# ProPrj__3_1_MIPI.net
KiCad netlist of a schematic drawn in EasyEDA Pro
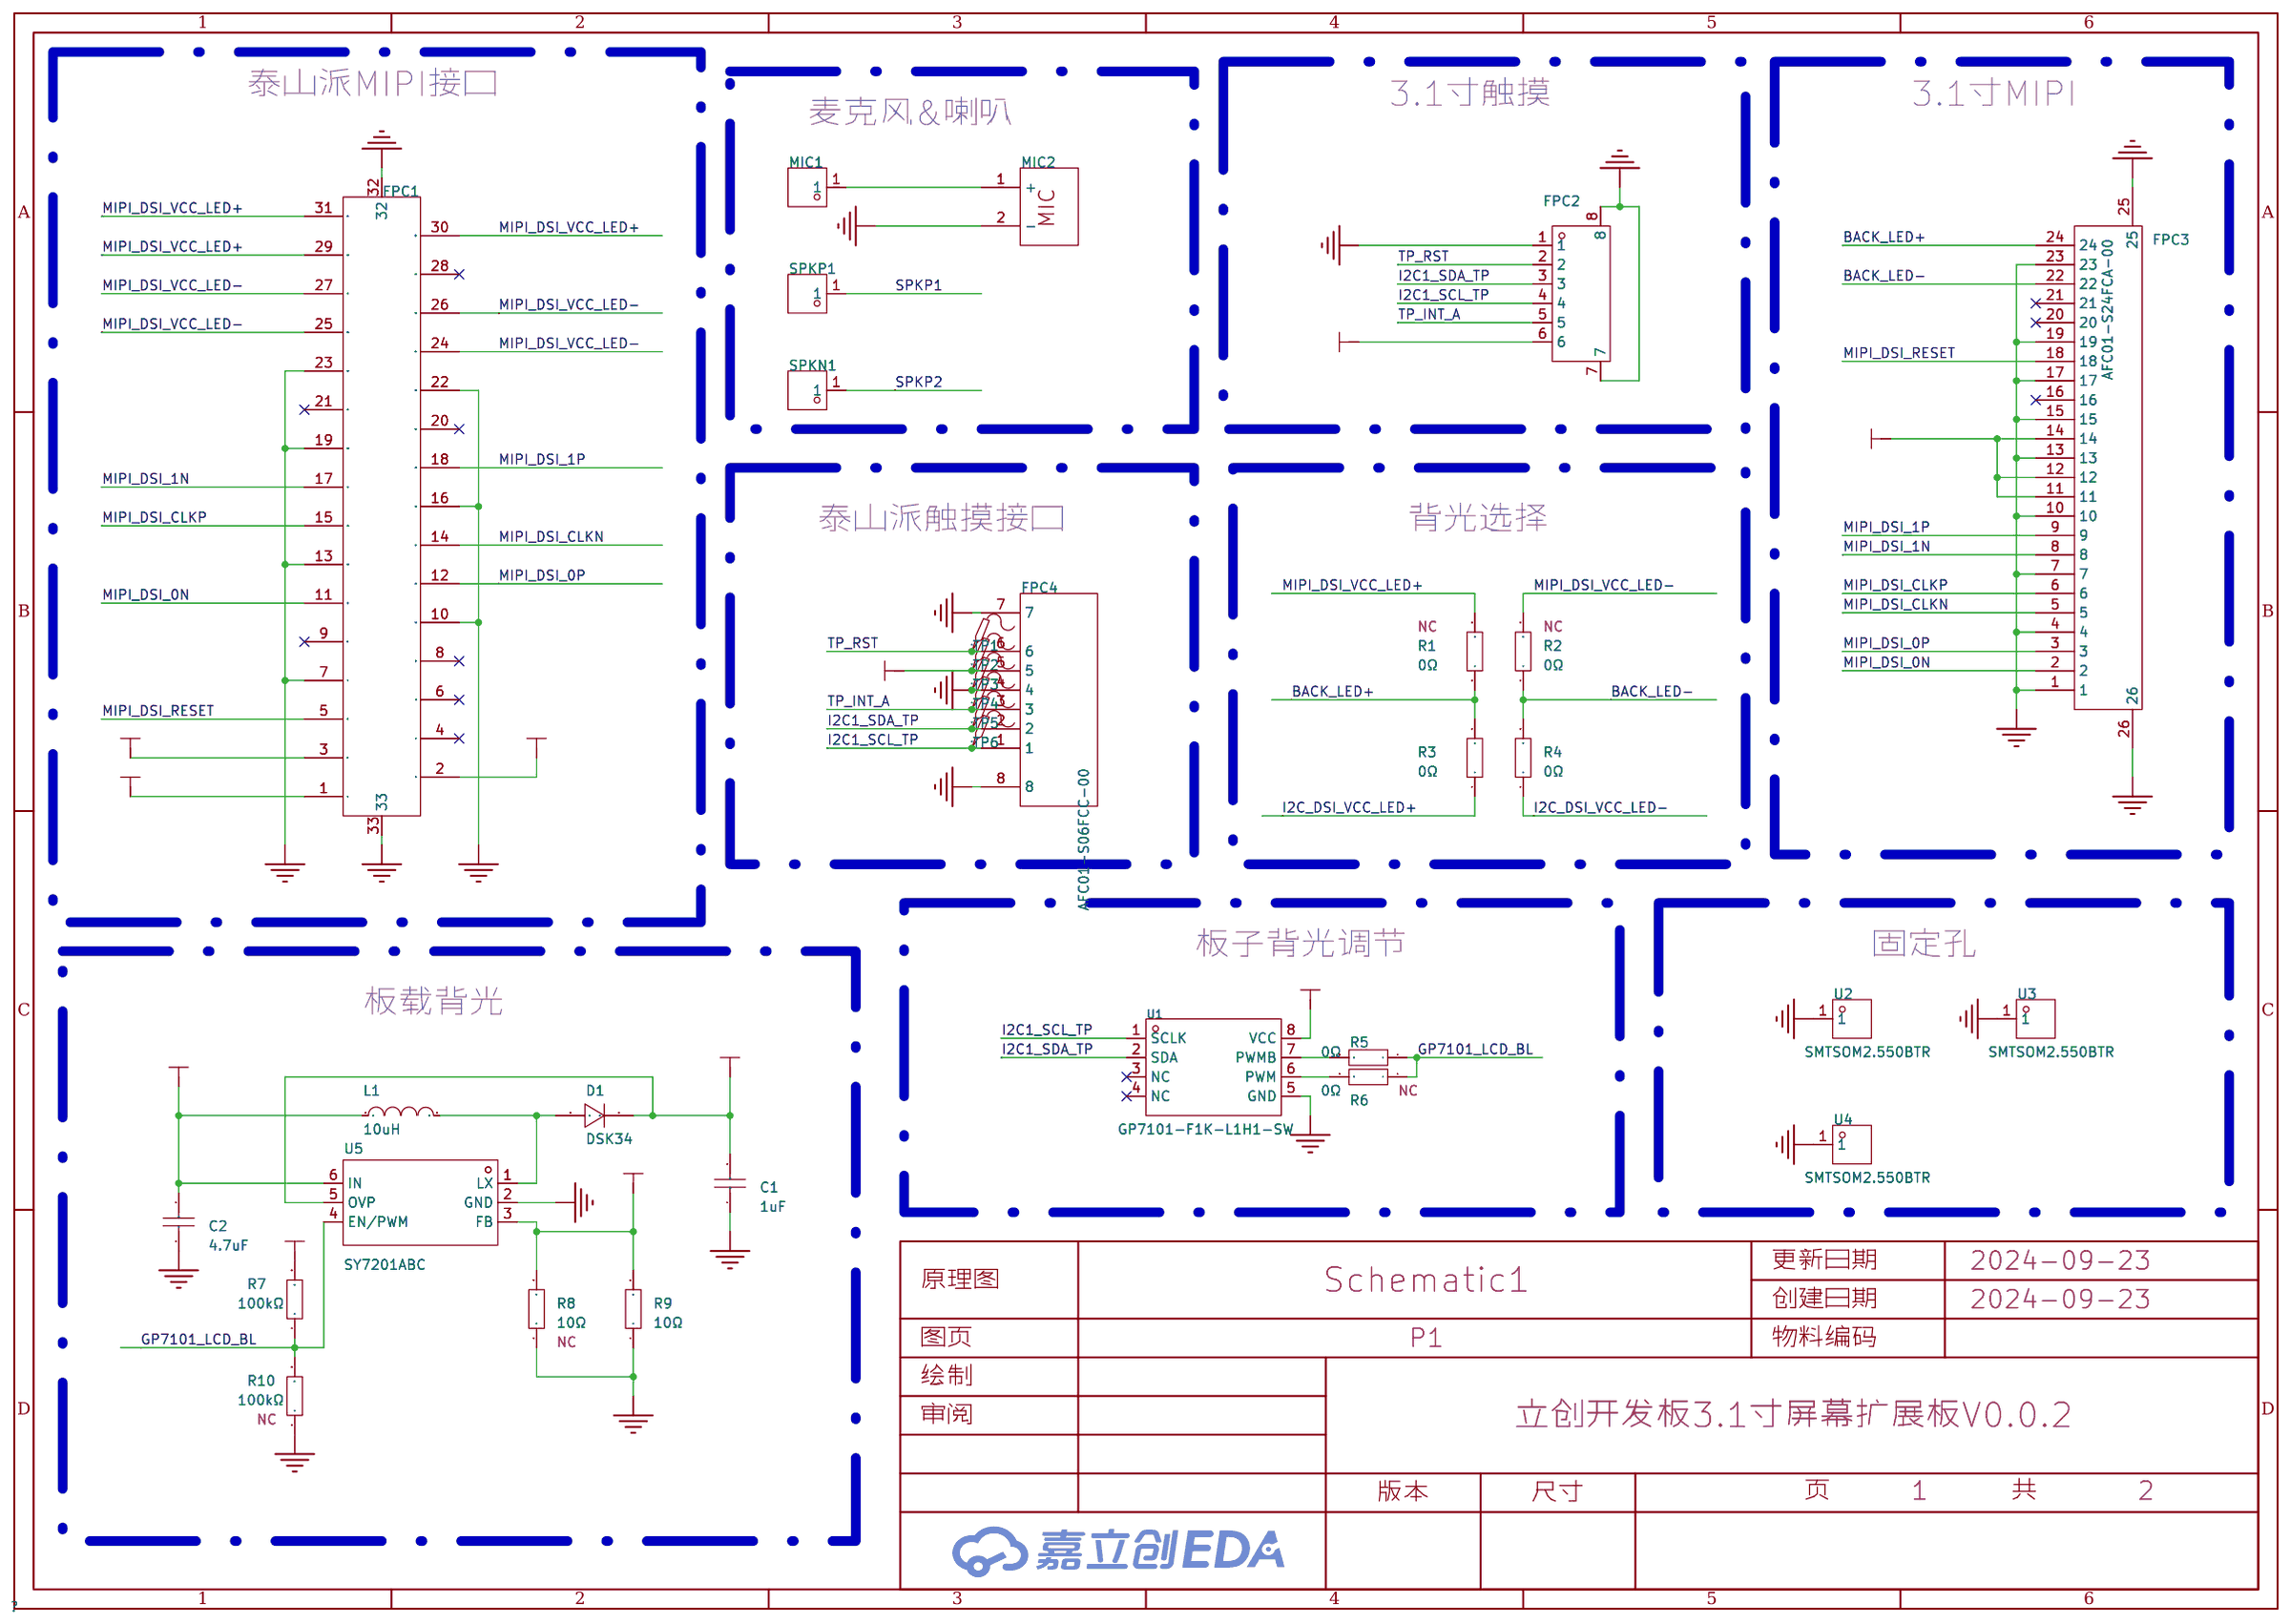
[diagram p0: P1]
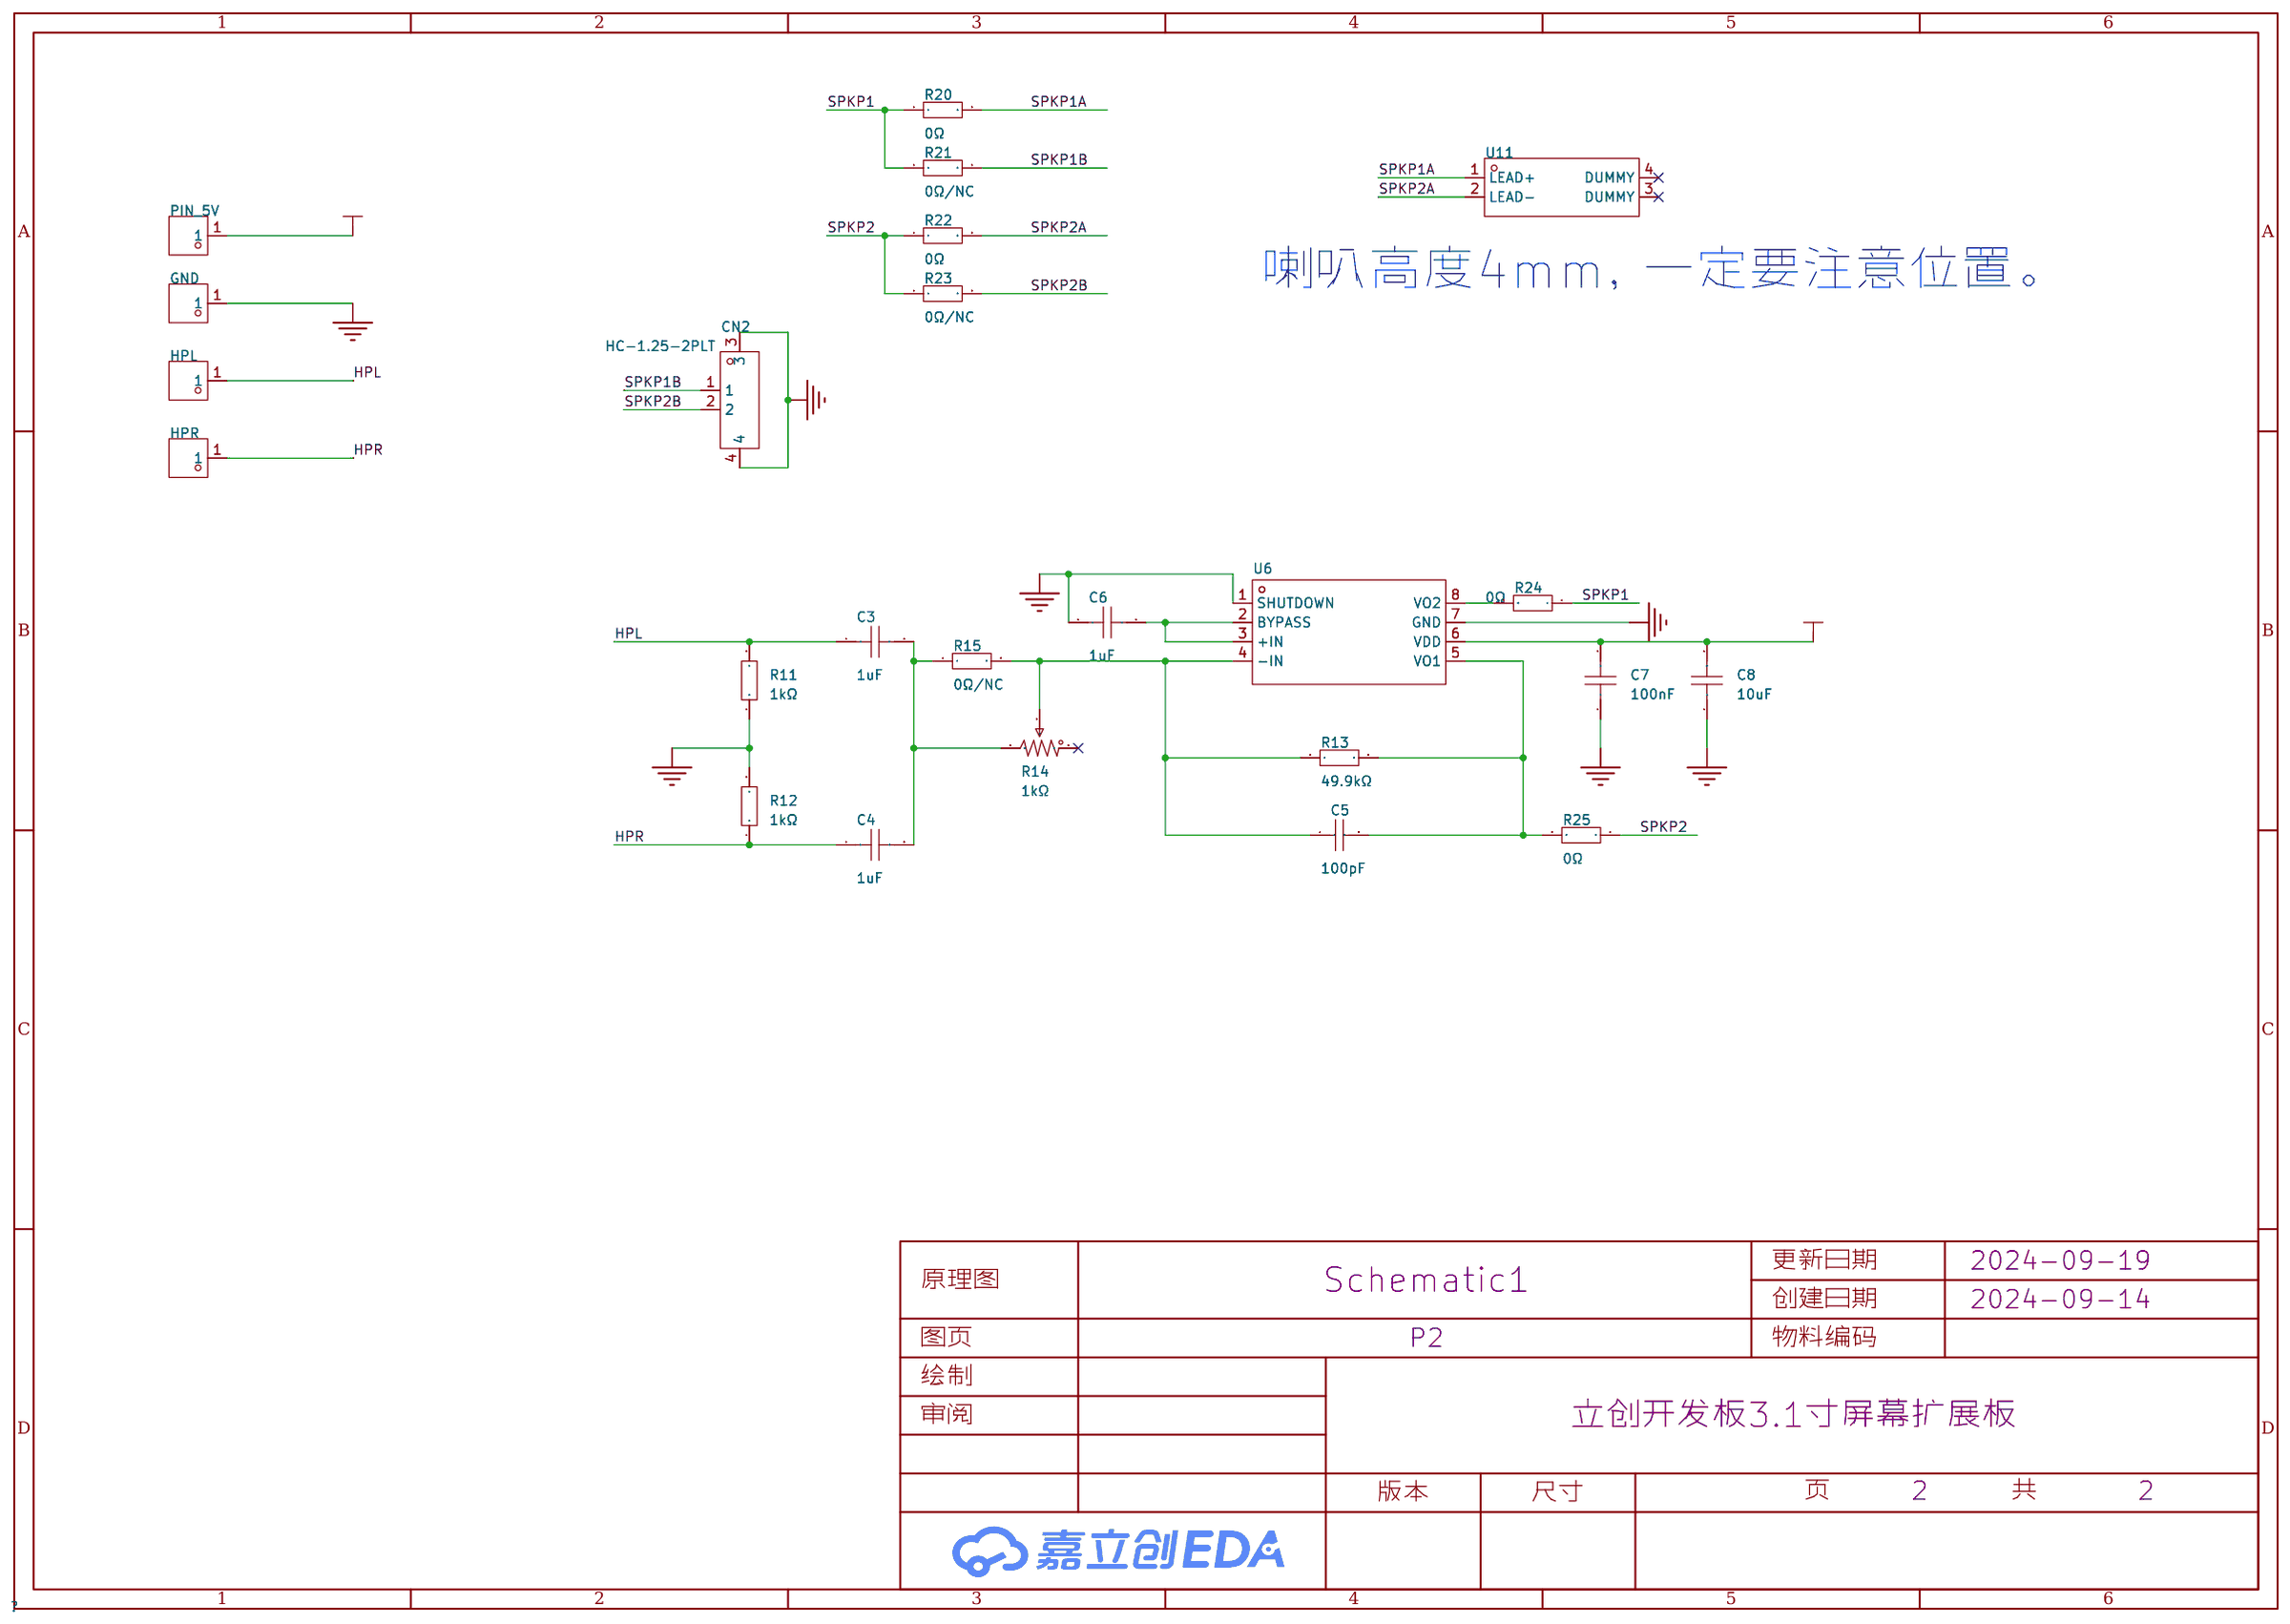
[diagram p1: P2]

(export (version "E")
  (design (tool "Eeschema 10.0.6"))
  (components
    (comp (ref "C1")
      (value "1uF")
      (footprint "easyedapro:C0805")
      (description "容值:1uF;精度:±10%;额定电压:50V;材质(温度系数):X7R;")
      (fields
        (field (name "Manufacturer Part") "CL21B105KBFNNNE")
        (field (name "Manufacturer") "SAMSUNG(三星)")
      )
      (libsource (lib "easyedapro") (part "CL21B105KBFNNNE"))
    )
    (comp (ref "C2")
      (value "4.7uF")
      (footprint "easyedapro:C0805")
      (description "容值:4.7uF;精度:±10%;额定电压:25V;材质(温度系数):X5R;")
      (fields
        (field (name "Manufacturer Part") "CL21A475KAQNNNE")
        (field (name "Manufacturer") "SAMSUNG(三星)")
      )
      (libsource (lib "easyedapro") (part "CL21A475KAQNNNE"))
    )
    (comp (ref "D1")
      (value "DSK34")
      (description "二极管配置:-;直流反向耐压(Vr):1kV;平均整流电流(Io):1A;正向压降(Vf):1.1V@1A;反向电流(Ir):10uA@1kV;")
      (fields (field (name "Manufacturer") "TWGMC(台湾迪嘉)"))
      (libsource (lib "easyedapro") (part "sm4007pl"))
    )
    (comp (ref "FPC1")
      (value "AFE03-S31FMA-1H")
      (footprint "easyedapro:FPC-SMD_P0.30-31P_FGS-XJ-H1.0")
      (description "间距:0.3mm;触点数量:31;锁定特性:翻盖式;安装类型:卧贴;触点类型:下接;")
      (fields (field (name "Manufacturer") "JS(钜硕电子)"))
      (libsource (lib "easyedapro") (part "AFE03-S31FMA-1H"))
    )
    (comp (ref "FPC2")
      (value "FPC-05F-6PH20")
      (footprint "easyedapro:FPC-SMD_6P-P0.50_XUNPU_FPC-05F-6PH20")
      (description "间距:0.5mm;触点数量:6P;锁定特性:翻盖式;触点类型:下接;安装类型:卧贴;工作温度范围:-25°C~+85°C;")
      (fields (field (name "Manufacturer") "XUNPU(讯普)"))
      (libsource (lib "easyedapro") (part "FPC-05F-6PH20"))
    )
    (comp (ref "FPC3")
      (value "AFC01-S24FCA-00")
      (footprint "easyedapro:FPC-SMD_P0.50-24P_FGS-XJ-H2.0")
      (description "间距:0.5mm;触点数量:24P;锁定特性:翻盖式;触点类型:下接;安装类型:卧贴;")
      (fields (field (name "Manufacturer") "JS(钜硕电子)"))
      (libsource (lib "easyedapro") (part "AFC01-S24FCA-00"))
    )
    (comp (ref "FPC4")
      (value "AFC01-S06FCC-00")
      (footprint "easyedapro:FPC-SMD_AFC01-S06FCC-00")
      (description "间距:0.5mm;触点数量:6;锁定特性:翻盖式;安装类型:卧贴;触点类型:下接;")
      (fields (field (name "Manufacturer") "JS(钜硕电子)"))
      (libsource (lib "easyedapro") (part "AFC01-S06FCC-00"))
    )
    (comp (ref "L1")
      (value "10uH")
      (fields
        (field (name "Manufacturer Part") "WPN252012H100MT")
        (field (name "Manufacturer") "Sunlord(顺络)")
      )
      (libsource (lib "easyedapro") (part "mlz2012n100lt000"))
    )
    (comp (ref "MIC1")
      (value "YTC1P-3010-01")
      (footprint "easyedapro:TESTPOINT-SMD_BD2.0_C9900030651")
      (description "类型:弹簧顶针(POGO PIN);PIN位数:单PIN位;全长/全高:4mm;额定电流:2.5A;额定电压:12V;触头材质:黄铜;触头镀层:金;")
      (fields (field (name "Manufacturer") "YIYUAN(怡远)"))
      (libsource (lib "easyedapro") (part "YTC1P-3010-01"))
    )
    (comp (ref "MIC2")
      (value "B4013AM423-008")
      (footprint "easyedapro:MIC-SMD_BD4.0_B4013AM423-008")
      (fields (field (name "Manufacturer") "Goertek(歌尔)"))
      (libsource (lib "easyedapro") (part "B4013AM423-008"))
    )
    (comp (ref "R1")
      (value "0Ω")
      (footprint "easyedapro:R0805")
      (description "电阻类型:厚膜电阻;阻值:0Ω;精度:±1%;功率:125mW;最大工作电压:150V;温度系数:±800ppm/°C;")
      (fields
        (field (name "Manufacturer Part") "0805W8F0000T5E")
        (field (name "Manufacturer") "UNI-ROYAL(厚声)")
        (field (name "Supplier Part") "NC")
      )
      (libsource (lib "easyedapro") (part "0805W8F0000T5E"))
    )
    (comp (ref "R2")
      (value "0Ω")
      (footprint "easyedapro:R0805")
      (description "电阻类型:厚膜电阻;阻值:0Ω;精度:±1%;功率:125mW;最大工作电压:150V;温度系数:±800ppm/°C;")
      (fields
        (field (name "Manufacturer Part") "0805W8F0000T5E")
        (field (name "Manufacturer") "UNI-ROYAL(厚声)")
        (field (name "Supplier Part") "NC")
      )
      (libsource (lib "easyedapro") (part "0805W8F0000T5E"))
    )
    (comp (ref "R3")
      (value "0Ω")
      (footprint "easyedapro:R0805")
      (description "电阻类型:厚膜电阻;阻值:0Ω;精度:±1%;功率:125mW;最大工作电压:150V;温度系数:±800ppm/°C;")
      (fields
        (field (name "Manufacturer Part") "0805W8F0000T5E")
        (field (name "Manufacturer") "UNI-ROYAL(厚声)")
      )
      (libsource (lib "easyedapro") (part "0805W8F0000T5E"))
    )
    (comp (ref "R4")
      (value "0Ω")
      (footprint "easyedapro:R0805")
      (description "电阻类型:厚膜电阻;阻值:0Ω;精度:±1%;功率:125mW;最大工作电压:150V;温度系数:±800ppm/°C;")
      (fields
        (field (name "Manufacturer Part") "0805W8F0000T5E")
        (field (name "Manufacturer") "UNI-ROYAL(厚声)")
      )
      (libsource (lib "easyedapro") (part "0805W8F0000T5E"))
    )
    (comp (ref "R5")
      (value "0Ω")
      (footprint "easyedapro:R0805")
      (description "电阻类型:厚膜电阻;阻值:0Ω;精度:±1%;功率:125mW;最大工作电压:150V;温度系数:±800ppm/°C;")
      (fields
        (field (name "Manufacturer Part") "0805W8F0000T5E")
        (field (name "Manufacturer") "UNI-ROYAL(厚声)")
      )
      (libsource (lib "easyedapro") (part "0805W8F0000T5E"))
    )
    (comp (ref "R6")
      (value "0Ω")
      (footprint "easyedapro:R0805")
      (description "电阻类型:厚膜电阻;阻值:0Ω;精度:±1%;功率:125mW;最大工作电压:150V;温度系数:±800ppm/°C;")
      (fields
        (field (name "Manufacturer Part") "0805W8F0000T5E")
        (field (name "Manufacturer") "UNI-ROYAL(厚声)")
        (field (name "Supplier Part") "NC")
      )
      (libsource (lib "easyedapro") (part "0805W8F0000T5E"))
    )
    (comp (ref "R7")
      (value "100kΩ")
      (footprint "easyedapro:R0805")
      (description "电阻类型:厚膜电阻;阻值:100kΩ;精度:±1%;功率:125mW;最大工作电压:150V;温度系数:±100ppm/°C;")
      (fields
        (field (name "Manufacturer Part") "0805W8F1003T5E")
        (field (name "Manufacturer") "UNI-ROYAL(厚声)")
      )
      (libsource (lib "easyedapro") (part "0805W8F1003T5E_C149504"))
    )
    (comp (ref "R8")
      (value "10Ω")
      (footprint "easyedapro:R0805_NEW")
      (description "电阻类型:厚膜电阻;阻值:10Ω;精度:±1%;功率:125mW;最大工作电压:150V;温度系数:±200ppm/°C;")
      (fields
        (field (name "Manufacturer Part") "0805W8F100JT5E")
        (field (name "Manufacturer") "UNI-ROYAL(厚声)")
        (field (name "Supplier Part") "NC")
      )
      (libsource (lib "easyedapro") (part "0805W8F100JT5E"))
    )
    (comp (ref "R9")
      (value "10Ω")
      (footprint "easyedapro:R0805_NEW")
      (description "电阻类型:厚膜电阻;阻值:10Ω;精度:±1%;功率:125mW;最大工作电压:150V;温度系数:±200ppm/°C;")
      (fields
        (field (name "Manufacturer Part") "0805W8F100JT5E")
        (field (name "Manufacturer") "UNI-ROYAL(厚声)")
      )
      (libsource (lib "easyedapro") (part "0805W8F100JT5E"))
    )
    (comp (ref "R10")
      (value "100kΩ")
      (footprint "easyedapro:R0805")
      (description "电阻类型:厚膜电阻;阻值:100kΩ;精度:±1%;功率:125mW;最大工作电压:150V;温度系数:±100ppm/°C;")
      (fields
        (field (name "Manufacturer Part") "0805W8F1003T5E")
        (field (name "Manufacturer") "UNI-ROYAL(厚声)")
        (field (name "Supplier Part") "NC")
      )
      (libsource (lib "easyedapro") (part "0805W8F1003T5E_C149504"))
    )
    (comp (ref "SPKN1")
      (value "YTC1P-3010-01")
      (footprint "easyedapro:TESTPOINT-SMD_BD2.0_C9900030651")
      (description "类型:弹簧顶针(POGO PIN);PIN位数:单PIN位;全长/全高:4mm;额定电流:2.5A;额定电压:12V;触头材质:黄铜;触头镀层:金;")
      (fields (field (name "Manufacturer") "YIYUAN(怡远)"))
      (libsource (lib "easyedapro") (part "YTC1P-3010-01"))
    )
    (comp (ref "SPKP1")
      (value "YTC1P-3010-01")
      (footprint "easyedapro:TESTPOINT-SMD_BD2.0_C9900030651")
      (description "类型:弹簧顶针(POGO PIN);PIN位数:单PIN位;全长/全高:4mm;额定电流:2.5A;额定电压:12V;触头材质:黄铜;触头镀层:金;")
      (fields (field (name "Manufacturer") "YIYUAN(怡远)"))
      (libsource (lib "easyedapro") (part "YTC1P-3010-01"))
    )
    (comp (ref "TP1")
      (value "~")
      (footprint "easyedapro:Test-Point-0.5mm")
      (description "Test Point 测试点")
      (libsource (lib "easyedapro") (part "Test-Point"))
    )
    (comp (ref "TP2")
      (value "~")
      (footprint "easyedapro:Test-Point-0.5mm")
      (description "Test Point 测试点")
      (libsource (lib "easyedapro") (part "Test-Point"))
    )
    (comp (ref "TP3")
      (value "~")
      (footprint "easyedapro:Test-Point-0.5mm")
      (description "Test Point 测试点")
      (libsource (lib "easyedapro") (part "Test-Point"))
    )
    (comp (ref "TP4")
      (value "~")
      (footprint "easyedapro:Test-Point-0.5mm")
      (description "Test Point 测试点")
      (libsource (lib "easyedapro") (part "Test-Point"))
    )
    (comp (ref "TP5")
      (value "~")
      (footprint "easyedapro:Test-Point-0.5mm")
      (description "Test Point 测试点")
      (libsource (lib "easyedapro") (part "Test-Point"))
    )
    (comp (ref "TP6")
      (value "~")
      (footprint "easyedapro:Test-Point-0.5mm")
      (description "Test Point 测试点")
      (libsource (lib "easyedapro") (part "Test-Point"))
    )
    (comp (ref "U1")
      (value "GP7101-F1K-L1H1-SW")
      (footprint "easyedapro:SOIC-8_L4.9-W3.9-P1.27-LS6.0-BL")
      (description "数模转换芯片ADC@@通过I2C进行数据输入，线性转换成0%-100%占空比的PWM信号输出")
      (fields (field (name "Manufacturer") "Guestgood(客益)"))
      (libsource (lib "easyedapro") (part "GP7101-F1K-L1H1-SW"))
    )
    (comp (ref "U2")
      (value "SMTSOM2.550BTR")
      (footprint "easyedapro:SMD_BD4.4-L4.4-D2.8")
      (description "M2x4.35xL5+1.4")
      (fields (field (name "Manufacturer") "YIYUAN(怡远)"))
      (libsource (lib "easyedapro") (part "SMTWE205MTJ"))
    )
    (comp (ref "U3")
      (value "SMTSOM2.550BTR")
      (footprint "easyedapro:SMD_BD4.4-L4.4-D2.8")
      (description "M2x4.35xL5+1.4")
      (fields (field (name "Manufacturer") "YIYUAN(怡远)"))
      (libsource (lib "easyedapro") (part "SMTWE205MTJ"))
    )
    (comp (ref "U4")
      (value "SMTSOM2.550BTR")
      (footprint "easyedapro:SMD_BD4.4-L4.4-D2.8")
      (description "M2x4.35xL5+1.4")
      (fields (field (name "Manufacturer") "YIYUAN(怡远)"))
      (libsource (lib "easyedapro") (part "SMTWE205MTJ"))
    )
    (comp (ref "U5")
      (value "SY7201ABC")
      (footprint "easyedapro:SOT-23-6_L2.9-W1.6-P0.95-LS2.8-BR")
      (description "30V 大电流LED驱动IC")
      (fields (field (name "Manufacturer") "silergy(矽力杰)"))
      (libsource (lib "easyedapro") (part "SY7201ABC"))
    )
    (comp (ref "C3")
      (value "1uF")
      (footprint "easyedapro:C0603")
      (description "容值:1uF;精度:±10%;额定电压:50V;材质(温度系数):X5R;")
      (fields
        (field (name "Manufacturer Part") "CL10A105KB8NNNC")
        (field (name "Manufacturer") "SAMSUNG(三星)")
      )
      (libsource (lib "easyedapro") (part "CL10A105KB8NNNC"))
    )
    (comp (ref "C4")
      (value "1uF")
      (footprint "easyedapro:C0603")
      (description "容值:1uF;精度:±10%;额定电压:50V;材质(温度系数):X5R;")
      (fields
        (field (name "Manufacturer Part") "CL10A105KB8NNNC")
        (field (name "Manufacturer") "SAMSUNG(三星)")
      )
      (libsource (lib "easyedapro") (part "CL10A105KB8NNNC"))
    )
    (comp (ref "C5")
      (value "100pF")
      (footprint "easyedapro:C0603")
      (description "容值:100pF;精度:±5%;额定电压:50V;材质(温度系数):C0G;")
      (fields
        (field (name "Manufacturer Part") "CL10C101JB8NNNC")
        (field (name "Manufacturer") "SAMSUNG(三星)")
      )
      (libsource (lib "easyedapro") (part "CL10C101JB8NNNC"))
    )
    (comp (ref "C6")
      (value "1uF")
      (footprint "easyedapro:C0603")
      (description "容值:1uF;精度:±10%;额定电压:50V;材质(温度系数):X5R;")
      (fields
        (field (name "Manufacturer Part") "CL10A105KB8NNNC")
        (field (name "Manufacturer") "SAMSUNG(三星)")
      )
      (libsource (lib "easyedapro") (part "CL10A105KB8NNNC"))
    )
    (comp (ref "C7")
      (value "100nF")
      (footprint "easyedapro:C0603")
      (description "容值:100nF;精度:±10%;额定电压:50V;材质(温度系数):X7R;")
      (fields
        (field (name "Manufacturer Part") "CC0603KRX7R9BB104")
        (field (name "Manufacturer") "YAGEO(国巨)")
      )
      (libsource (lib "easyedapro") (part "CC0603KRX7R9BB104"))
    )
    (comp (ref "C8")
      (value "10uF")
      (footprint "easyedapro:C0603")
      (description "容值:10uF;精度:±20%;额定电压:25V;材质(温度系数):X5R;")
      (fields
        (field (name "Manufacturer Part") "CL10A106MA8NRNC")
        (field (name "Manufacturer") "SAMSUNG(三星)")
      )
      (libsource (lib "easyedapro") (part "CL10A106MA8NRNC"))
    )
    (comp (ref "CN2")
      (value "HC-1.25-2PLT")
      (footprint "easyedapro:CONN-SMD_HC-1.25-2PLT")
      (fields (field (name "Manufacturer") "HCTL(华灿天禄)"))
      (libsource (lib "easyedapro") (part "HC-1.25-2PLT"))
    )
    (comp (ref "GND")
      (value "YTC1P-3010-01")
      (footprint "easyedapro:TESTPOINT-SMD_BD2.0_C9900030651")
      (description "类型:弹簧顶针(POGO PIN);PIN位数:单PIN位;全长/全高:4mm;额定电流:2.5A;额定电压:12V;触头材质:黄铜;触头镀层:金;")
      (fields (field (name "Manufacturer") "YIYUAN(怡远)"))
      (libsource (lib "easyedapro") (part "YTC1P-3010-01"))
    )
    (comp (ref "HPL")
      (value "YTC1P-3010-01")
      (footprint "easyedapro:TESTPOINT-SMD_BD2.0_C9900030651")
      (description "类型:弹簧顶针(POGO PIN);PIN位数:单PIN位;全长/全高:4mm;额定电流:2.5A;额定电压:12V;触头材质:黄铜;触头镀层:金;")
      (fields (field (name "Manufacturer") "YIYUAN(怡远)"))
      (libsource (lib "easyedapro") (part "YTC1P-3010-01"))
    )
    (comp (ref "HPR")
      (value "YTC1P-3010-01")
      (footprint "easyedapro:TESTPOINT-SMD_BD2.0_C9900030651")
      (description "类型:弹簧顶针(POGO PIN);PIN位数:单PIN位;全长/全高:4mm;额定电流:2.5A;额定电压:12V;触头材质:黄铜;触头镀层:金;")
      (fields (field (name "Manufacturer") "YIYUAN(怡远)"))
      (libsource (lib "easyedapro") (part "YTC1P-3010-01"))
    )
    (comp (ref "PIN_5V")
      (value "YTC1P-3010-01")
      (footprint "easyedapro:TESTPOINT-SMD_BD2.0_C9900030651")
      (description "类型:弹簧顶针(POGO PIN);PIN位数:单PIN位;全长/全高:4mm;额定电流:2.5A;额定电压:12V;触头材质:黄铜;触头镀层:金;")
      (fields (field (name "Manufacturer") "YIYUAN(怡远)"))
      (libsource (lib "easyedapro") (part "YTC1P-3010-01"))
    )
    (comp (ref "R11")
      (value "1kΩ")
      (footprint "easyedapro:R0603")
      (description "电阻类型:厚膜电阻;阻值:1kΩ;精度:±1%;功率:100mW;最大工作电压:75V;温度系数:±100ppm/°C;")
      (fields
        (field (name "Manufacturer Part") "0603WAF1001T5E")
        (field (name "Manufacturer") "UNI-ROYAL(厚声)")
      )
      (libsource (lib "easyedapro") (part "0603WAF1001T5E"))
    )
    (comp (ref "R12")
      (value "1kΩ")
      (footprint "easyedapro:R0603")
      (description "电阻类型:厚膜电阻;阻值:1kΩ;精度:±1%;功率:100mW;最大工作电压:75V;温度系数:±100ppm/°C;")
      (fields
        (field (name "Manufacturer Part") "0603WAF1001T5E")
        (field (name "Manufacturer") "UNI-ROYAL(厚声)")
      )
      (libsource (lib "easyedapro") (part "0603WAF1001T5E"))
    )
    (comp (ref "R13")
      (value "49.9kΩ")
      (footprint "easyedapro:R0603")
      (description "电阻类型:厚膜电阻;阻值:49.9kΩ;精度:±1%;功率:100mW;最大工作电压:75V;温度系数:±100ppm/°C;")
      (fields
        (field (name "Manufacturer Part") "0603WAF4992T5E")
        (field (name "Manufacturer") "UNI-ROYAL(厚声)")
      )
      (libsource (lib "easyedapro") (part "0603WAF4992T5E"))
    )
    (comp (ref "R14")
      (value "1kΩ")
      (footprint "easyedapro:RES-ADJ-SMD_3P-L3.8-W3.6-P1.90-BL")
      (description "阻值:1kΩ;精度:±25%;功率:150mW;温度系数:±250ppm/°C;")
      (fields (field (name "Manufacturer Part") "TC33X-2-102E") (field (name "Manufacturer") "BOURNS"))
      (libsource (lib "easyedapro") (part "TC33X-2-102E"))
    )
    (comp (ref "R15")
      (value "0Ω/NC")
      (footprint "easyedapro:R0603")
      (description "电阻类型:厚膜电阻;阻值:0Ω;精度:±1%;功率:100mW;最大工作电压:75V;")
      (fields
        (field (name "Manufacturer Part") "0603WAF0000T5E")
        (field (name "Manufacturer") "UNI-ROYAL(厚声)")
      )
      (libsource (lib "easyedapro") (part "0603WAF0000T5E"))
    )
    (comp (ref "R20")
      (value "0Ω")
      (footprint "easyedapro:R0603")
      (description "电阻类型:厚膜电阻;阻值:0Ω;精度:±1%;功率:100mW;最大工作电压:75V;")
      (fields
        (field (name "Manufacturer Part") "0603WAF0000T5E")
        (field (name "Manufacturer") "UNI-ROYAL(厚声)")
      )
      (libsource (lib "easyedapro") (part "0603WAF0000T5E"))
    )
    (comp (ref "R21")
      (value "0Ω/NC")
      (footprint "easyedapro:R0603")
      (description "电阻类型:厚膜电阻;阻值:0Ω;精度:±1%;功率:100mW;最大工作电压:75V;")
      (fields
        (field (name "Manufacturer Part") "0603WAF0000T5E")
        (field (name "Manufacturer") "UNI-ROYAL(厚声)")
      )
      (libsource (lib "easyedapro") (part "0603WAF0000T5E"))
    )
    (comp (ref "R22")
      (value "0Ω")
      (footprint "easyedapro:R0603")
      (description "电阻类型:厚膜电阻;阻值:0Ω;精度:±1%;功率:100mW;最大工作电压:75V;")
      (fields
        (field (name "Manufacturer Part") "0603WAF0000T5E")
        (field (name "Manufacturer") "UNI-ROYAL(厚声)")
      )
      (libsource (lib "easyedapro") (part "0603WAF0000T5E"))
    )
    (comp (ref "R23")
      (value "0Ω/NC")
      (footprint "easyedapro:R0603")
      (description "电阻类型:厚膜电阻;阻值:0Ω;精度:±1%;功率:100mW;最大工作电压:75V;")
      (fields
        (field (name "Manufacturer Part") "0603WAF0000T5E")
        (field (name "Manufacturer") "UNI-ROYAL(厚声)")
      )
      (libsource (lib "easyedapro") (part "0603WAF0000T5E"))
    )
    (comp (ref "R24")
      (value "0Ω")
      (footprint "easyedapro:R0805")
      (description "电阻类型:厚膜电阻;阻值:0Ω;精度:±1%;功率:125mW;最大工作电压:150V;温度系数:±800ppm/°C;")
      (fields
        (field (name "Manufacturer Part") "0805W8F0000T5E")
        (field (name "Manufacturer") "UNI-ROYAL(厚声)")
      )
      (libsource (lib "easyedapro") (part "0805W8F0000T5E"))
    )
    (comp (ref "R25")
      (value "0Ω")
      (footprint "easyedapro:R0805")
      (description "电阻类型:厚膜电阻;阻值:0Ω;精度:±1%;功率:125mW;最大工作电压:150V;温度系数:±800ppm/°C;")
      (fields
        (field (name "Manufacturer Part") "0805W8F0000T5E")
        (field (name "Manufacturer") "UNI-ROYAL(厚声)")
      )
      (libsource (lib "easyedapro") (part "0805W8F0000T5E"))
    )
    (comp (ref "U6")
      (value "SC8002B")
      (footprint "easyedapro:SOP-8_L4.9-W3.9-P1.27-LS6.0-BL")
      (description "功放类型:-;扬声器通道数:单声道;输出功率:2.5Wx1@4Ω;")
      (fields (field (name "Manufacturer") "FM(富满)"))
      (libsource (lib "easyedapro") (part "SC8002B"))
    )
    (comp (ref "U11")
      (value "KLJ-01304T-08R07W")
      (footprint "easyedapro:BUZ-SMD_4P-L13.0-W13.0-P11.4-BL")
      (description "产品一致性好、抗老化能力强")
      (fields (field (name "Manufacturer") "KELIKING(凯丽金)"))
      (libsource (lib "easyedapro") (part "KLJ-01304T-08R07W"))
    )
  )
  (nets
    (net (code "1") (name "BACK_LED+") (class "Default")
      (node (ref "FPC3") (pin "24") (pinfunction "24_24") (pintype "unspecified"))
      (node (ref "R1") (pin "1") (pinfunction "1_1") (pintype "input"))
      (node (ref "R3") (pin "2") (pinfunction "2_2") (pintype "input"))
    )
    (net (code "2") (name "BACK_LED-") (class "Default")
      (node (ref "FPC3") (pin "22") (pinfunction "22_22") (pintype "unspecified"))
      (node (ref "R2") (pin "1") (pinfunction "1_1") (pintype "input"))
      (node (ref "R4") (pin "2") (pinfunction "2_2") (pintype "input"))
    )
    (net (code "3") (name "GND") (class "Default")
      (node (ref "C1") (pin "1") (pinfunction "1_1") (pintype "input"))
      (node (ref "C2") (pin "1") (pinfunction "1_1") (pintype "input"))
      (node (ref "C6") (pin "1") (pinfunction "1_1") (pintype "unspecified"))
      (node (ref "C7") (pin "1") (pinfunction "1_1") (pintype "unspecified"))
      (node (ref "C8") (pin "1") (pinfunction "1_1") (pintype "unspecified"))
      (node (ref "CN2") (pin "3") (pinfunction "3_3") (pintype "unspecified"))
      (node (ref "CN2") (pin "4") (pinfunction "4_4") (pintype "unspecified"))
      (node (ref "FPC1") (pin "10") (pinfunction "10_10") (pintype "unspecified"))
      (node (ref "FPC1") (pin "13") (pinfunction "13_13") (pintype "unspecified"))
      (node (ref "FPC1") (pin "16") (pinfunction "16_16") (pintype "unspecified"))
      (node (ref "FPC1") (pin "19") (pinfunction "19_19") (pintype "unspecified"))
      (node (ref "FPC1") (pin "22") (pinfunction "22_22") (pintype "unspecified"))
      (node (ref "FPC1") (pin "23") (pinfunction "23_23") (pintype "unspecified"))
      (node (ref "FPC1") (pin "32") (pinfunction "32_32") (pintype "unspecified"))
      (node (ref "FPC1") (pin "33") (pinfunction "33_33") (pintype "unspecified"))
      (node (ref "FPC1") (pin "7") (pinfunction "7_7") (pintype "unspecified"))
      (node (ref "FPC2") (pin "1") (pinfunction "1_1") (pintype "unspecified"))
      (node (ref "FPC2") (pin "7") (pinfunction "7_7") (pintype "unspecified"))
      (node (ref "FPC2") (pin "8") (pinfunction "8_8") (pintype "unspecified"))
      (node (ref "FPC3") (pin "1") (pinfunction "1_1") (pintype "unspecified"))
      (node (ref "FPC3") (pin "10") (pinfunction "10_10") (pintype "unspecified"))
      (node (ref "FPC3") (pin "13") (pinfunction "13_13") (pintype "unspecified"))
      (node (ref "FPC3") (pin "15") (pinfunction "15_15") (pintype "unspecified"))
      (node (ref "FPC3") (pin "17") (pinfunction "17_17") (pintype "unspecified"))
      (node (ref "FPC3") (pin "19") (pinfunction "19_19") (pintype "unspecified"))
      (node (ref "FPC3") (pin "23") (pinfunction "23_23") (pintype "unspecified"))
      (node (ref "FPC3") (pin "25") (pinfunction "25_25") (pintype "unspecified"))
      (node (ref "FPC3") (pin "26") (pinfunction "26_26") (pintype "unspecified"))
      (node (ref "FPC3") (pin "4") (pinfunction "4_4") (pintype "unspecified"))
      (node (ref "FPC3") (pin "7") (pinfunction "7_7") (pintype "unspecified"))
      (node (ref "FPC4") (pin "4") (pinfunction "4_4") (pintype "input"))
      (node (ref "FPC4") (pin "7") (pinfunction "7_7") (pintype "input"))
      (node (ref "FPC4") (pin "8") (pinfunction "8_8") (pintype "input"))
      (node (ref "GND") (pin "1") (pinfunction "1_1") (pintype "unspecified"))
      (node (ref "MIC2") (pin "2") (pinfunction "-_2") (pintype "input"))
      (node (ref "R10") (pin "1") (pinfunction "1_1") (pintype "unspecified"))
      (node (ref "R11") (pin "1") (pinfunction "1_1") (pintype "input"))
      (node (ref "R12") (pin "2") (pinfunction "2_2") (pintype "input"))
      (node (ref "R8") (pin "1") (pinfunction "1_1") (pintype "input"))
      (node (ref "R9") (pin "1") (pinfunction "1_1") (pintype "input"))
      (node (ref "TP3") (pin "1") (pinfunction "1_1") (pintype "input"))
      (node (ref "U1") (pin "5") (pinfunction "GND_5") (pintype "input"))
      (node (ref "U2") (pin "1") (pinfunction "1_1") (pintype "unspecified"))
      (node (ref "U3") (pin "1") (pinfunction "1_1") (pintype "unspecified"))
      (node (ref "U4") (pin "1") (pinfunction "1_1") (pintype "unspecified"))
      (node (ref "U5") (pin "2") (pinfunction "GND_2") (pintype "input"))
      (node (ref "U6") (pin "1") (pinfunction "SHUTDOWN_1") (pintype "input"))
      (node (ref "U6") (pin "7") (pinfunction "GND_7") (pintype "input"))
    )
    (net (code "4") (name "GP7101_LCD_BL") (class "Default")
      (node (ref "R10") (pin "2") (pinfunction "2_2") (pintype "unspecified"))
      (node (ref "R5") (pin "1") (pinfunction "1_1") (pintype "input"))
      (node (ref "R6") (pin "1") (pinfunction "1_1") (pintype "input"))
      (node (ref "R7") (pin "1") (pinfunction "1_1") (pintype "unspecified"))
      (node (ref "U5") (pin "4") (pinfunction "EN/PWM_4") (pintype "input"))
    )
    (net (code "5") (name "HPL") (class "Default")
      (node (ref "C3") (pin "1") (pinfunction "1_1") (pintype "unspecified"))
      (node (ref "HPL") (pin "1") (pinfunction "1_1") (pintype "unspecified"))
      (node (ref "R11") (pin "2") (pinfunction "2_2") (pintype "input"))
    )
    (net (code "6") (name "HPR") (class "Default")
      (node (ref "C4") (pin "1") (pinfunction "1_1") (pintype "unspecified"))
      (node (ref "HPR") (pin "1") (pinfunction "1_1") (pintype "unspecified"))
      (node (ref "R12") (pin "1") (pinfunction "1_1") (pintype "input"))
    )
    (net (code "7") (name "I2C1_SCL_TP") (class "Default")
      (node (ref "FPC2") (pin "4") (pinfunction "4_4") (pintype "unspecified"))
      (node (ref "FPC4") (pin "1") (pinfunction "1_1") (pintype "input"))
      (node (ref "TP6") (pin "1") (pinfunction "1_1") (pintype "input"))
      (node (ref "U1") (pin "1") (pinfunction "SCLK_1") (pintype "input"))
    )
    (net (code "8") (name "I2C1_SDA_TP") (class "Default")
      (node (ref "FPC2") (pin "3") (pinfunction "3_3") (pintype "unspecified"))
      (node (ref "FPC4") (pin "2") (pinfunction "2_2") (pintype "input"))
      (node (ref "TP5") (pin "1") (pinfunction "1_1") (pintype "input"))
      (node (ref "U1") (pin "2") (pinfunction "SDA_2") (pintype "input"))
    )
    (net (code "9") (name "I2C_DSI_VCC_LED+") (class "Default")
      (node (ref "C1") (pin "2") (pinfunction "2_2") (pintype "input"))
      (node (ref "D1") (pin "1") (pinfunction "C_1") (pintype "input"))
      (node (ref "R3") (pin "1") (pinfunction "1_1") (pintype "input"))
      (node (ref "U5") (pin "5") (pinfunction "OVP_5") (pintype "input"))
    )
    (net (code "10") (name "I2C_DSI_VCC_LED-") (class "Default")
      (node (ref "R4") (pin "1") (pinfunction "1_1") (pintype "input"))
      (node (ref "R8") (pin "2") (pinfunction "2_2") (pintype "input"))
      (node (ref "R9") (pin "2") (pinfunction "2_2") (pintype "input"))
      (node (ref "U5") (pin "3") (pinfunction "FB_3") (pintype "input"))
    )
    (net (code "11") (name "MIPI_DSI_0N") (class "Default")
      (node (ref "FPC1") (pin "11") (pinfunction "11_11") (pintype "unspecified"))
      (node (ref "FPC3") (pin "2") (pinfunction "2_2") (pintype "unspecified"))
    )
    (net (code "12") (name "MIPI_DSI_0P") (class "Default")
      (node (ref "FPC1") (pin "12") (pinfunction "12_12") (pintype "unspecified"))
      (node (ref "FPC3") (pin "3") (pinfunction "3_3") (pintype "unspecified"))
    )
    (net (code "13") (name "MIPI_DSI_1N") (class "Default")
      (node (ref "FPC1") (pin "17") (pinfunction "17_17") (pintype "unspecified"))
      (node (ref "FPC3") (pin "8") (pinfunction "8_8") (pintype "unspecified"))
    )
    (net (code "14") (name "MIPI_DSI_1P") (class "Default")
      (node (ref "FPC1") (pin "18") (pinfunction "18_18") (pintype "unspecified"))
      (node (ref "FPC3") (pin "9") (pinfunction "9_9") (pintype "unspecified"))
    )
    (net (code "15") (name "MIPI_DSI_CLKN") (class "Default")
      (node (ref "FPC1") (pin "14") (pinfunction "14_14") (pintype "unspecified"))
      (node (ref "FPC3") (pin "5") (pinfunction "5_5") (pintype "unspecified"))
    )
    (net (code "16") (name "MIPI_DSI_CLKP") (class "Default")
      (node (ref "FPC1") (pin "15") (pinfunction "15_15") (pintype "unspecified"))
      (node (ref "FPC3") (pin "6") (pinfunction "6_6") (pintype "unspecified"))
    )
    (net (code "17") (name "MIPI_DSI_RESET") (class "Default")
      (node (ref "FPC1") (pin "5") (pinfunction "5_5") (pintype "unspecified"))
      (node (ref "FPC3") (pin "18") (pinfunction "18_18") (pintype "unspecified"))
    )
    (net (code "18") (name "MIPI_DSI_VCC_LED+") (class "Default")
      (node (ref "FPC1") (pin "29") (pinfunction "29_29") (pintype "unspecified"))
      (node (ref "FPC1") (pin "30") (pinfunction "30_30") (pintype "unspecified"))
      (node (ref "FPC1") (pin "31") (pinfunction "31_31") (pintype "unspecified"))
      (node (ref "R1") (pin "2") (pinfunction "2_2") (pintype "input"))
    )
    (net (code "19") (name "MIPI_DSI_VCC_LED-") (class "Default")
      (node (ref "FPC1") (pin "24") (pinfunction "24_24") (pintype "unspecified"))
      (node (ref "FPC1") (pin "25") (pinfunction "25_25") (pintype "unspecified"))
      (node (ref "FPC1") (pin "26") (pinfunction "26_26") (pintype "unspecified"))
      (node (ref "FPC1") (pin "27") (pinfunction "27_27") (pintype "unspecified"))
      (node (ref "R2") (pin "2") (pinfunction "2_2") (pintype "input"))
    )
    (net (code "20") (name "Net-(C3-Pad2)") (class "Default")
      (node (ref "C3") (pin "2") (pinfunction "2_2") (pintype "unspecified"))
      (node (ref "C4") (pin "2") (pinfunction "2_2") (pintype "unspecified"))
      (node (ref "R14") (pin "3") (pinfunction "3_3") (pintype "unspecified"))
      (node (ref "R15") (pin "1") (pinfunction "1_1") (pintype "input"))
    )
    (net (code "21") (name "Net-(D1-A)") (class "Default")
      (node (ref "D1") (pin "2") (pinfunction "A_2") (pintype "input"))
      (node (ref "L1") (pin "2") (pinfunction "2_2") (pintype "input"))
      (node (ref "U5") (pin "1") (pinfunction "LX_1") (pintype "input"))
    )
    (net (code "22") (name "Net-(MIC2-+)") (class "Default")
      (node (ref "MIC1") (pin "1") (pinfunction "1_1") (pintype "unspecified"))
      (node (ref "MIC2") (pin "1") (pinfunction "+_1") (pintype "input"))
    )
    (net (code "23") (name "Net-(U1-PWM)") (class "Default")
      (node (ref "R6") (pin "2") (pinfunction "2_2") (pintype "input"))
      (node (ref "U1") (pin "6") (pinfunction "PWM_6") (pintype "input"))
    )
    (net (code "24") (name "Net-(U1-PWMB)") (class "Default")
      (node (ref "R5") (pin "2") (pinfunction "2_2") (pintype "input"))
      (node (ref "U1") (pin "7") (pinfunction "PWMB_7") (pintype "input"))
    )
    (net (code "25") (name "Net-(U6-+IN)") (class "Default")
      (node (ref "C6") (pin "2") (pinfunction "2_2") (pintype "unspecified"))
      (node (ref "U6") (pin "2") (pinfunction "BYPASS_2") (pintype "input"))
      (node (ref "U6") (pin "3") (pinfunction "+IN_3") (pintype "input"))
    )
    (net (code "26") (name "Net-(U6--IN)") (class "Default")
      (node (ref "C5") (pin "1") (pinfunction "1_1") (pintype "input"))
      (node (ref "R13") (pin "1") (pinfunction "1_1") (pintype "input"))
      (node (ref "R14") (pin "2") (pinfunction "2_2") (pintype "unspecified"))
      (node (ref "R15") (pin "2") (pinfunction "2_2") (pintype "input"))
      (node (ref "U6") (pin "4") (pinfunction "-IN_4") (pintype "input"))
    )
    (net (code "27") (name "Net-(U6-VO1)") (class "Default")
      (node (ref "C5") (pin "2") (pinfunction "2_2") (pintype "input"))
      (node (ref "R13") (pin "2") (pinfunction "2_2") (pintype "input"))
      (node (ref "R25") (pin "2") (pinfunction "2_2") (pintype "input"))
      (node (ref "U6") (pin "5") (pinfunction "VO1_5") (pintype "input"))
    )
    (net (code "28") (name "Net-(U6-VO2)") (class "Default")
      (node (ref "R24") (pin "2") (pinfunction "2_2") (pintype "input"))
      (node (ref "U6") (pin "8") (pinfunction "VO2_8") (pintype "input"))
    )
    (net (code "29") (name "PIN_5V") (class "Default")
      (node (ref "C7") (pin "2") (pinfunction "2_2") (pintype "unspecified"))
      (node (ref "C8") (pin "2") (pinfunction "2_2") (pintype "unspecified"))
      (node (ref "PIN_5V") (pin "1") (pinfunction "1_1") (pintype "unspecified"))
      (node (ref "U6") (pin "6") (pinfunction "VDD_6") (pintype "input"))
    )
    (net (code "30") (name "SPKP1") (class "Default")
      (node (ref "R20") (pin "1") (pinfunction "1_1") (pintype "input"))
      (node (ref "R21") (pin "1") (pinfunction "1_1") (pintype "input"))
      (node (ref "R24") (pin "1") (pinfunction "1_1") (pintype "input"))
      (node (ref "SPKP1") (pin "1") (pinfunction "1_1") (pintype "unspecified"))
    )
    (net (code "31") (name "SPKP1A") (class "Default")
      (node (ref "R20") (pin "2") (pinfunction "2_2") (pintype "input"))
      (node (ref "U11") (pin "1") (pinfunction "LEAD+_1") (pintype "unspecified"))
    )
    (net (code "32") (name "SPKP1B") (class "Default")
      (node (ref "CN2") (pin "1") (pinfunction "1_1") (pintype "unspecified"))
      (node (ref "R21") (pin "2") (pinfunction "2_2") (pintype "input"))
    )
    (net (code "33") (name "SPKP2") (class "Default")
      (node (ref "R22") (pin "1") (pinfunction "1_1") (pintype "input"))
      (node (ref "R23") (pin "1") (pinfunction "1_1") (pintype "input"))
      (node (ref "R25") (pin "1") (pinfunction "1_1") (pintype "input"))
      (node (ref "SPKN1") (pin "1") (pinfunction "1_1") (pintype "unspecified"))
    )
    (net (code "34") (name "SPKP2A") (class "Default")
      (node (ref "R22") (pin "2") (pinfunction "2_2") (pintype "input"))
      (node (ref "U11") (pin "2") (pinfunction "LEAD-_2") (pintype "unspecified"))
    )
    (net (code "35") (name "SPKP2B") (class "Default")
      (node (ref "CN2") (pin "2") (pinfunction "2_2") (pintype "unspecified"))
      (node (ref "R23") (pin "2") (pinfunction "2_2") (pintype "input"))
    )
    (net (code "36") (name "TP_INT_A") (class "Default")
      (node (ref "FPC2") (pin "5") (pinfunction "5_5") (pintype "unspecified"))
      (node (ref "FPC4") (pin "3") (pinfunction "3_3") (pintype "input"))
      (node (ref "TP4") (pin "1") (pinfunction "1_1") (pintype "input"))
    )
    (net (code "37") (name "TP_RST") (class "Default")
      (node (ref "FPC2") (pin "2") (pinfunction "2_2") (pintype "unspecified"))
      (node (ref "FPC4") (pin "6") (pinfunction "6_6") (pintype "input"))
      (node (ref "TP1") (pin "1") (pinfunction "1_1") (pintype "input"))
    )
    (net (code "38") (name "VCC_3V3") (class "Default")
      (node (ref "C2") (pin "2") (pinfunction "2_2") (pintype "input"))
      (node (ref "FPC1") (pin "1") (pinfunction "1_1") (pintype "unspecified"))
      (node (ref "FPC1") (pin "2") (pinfunction "2_2") (pintype "unspecified"))
      (node (ref "FPC1") (pin "3") (pinfunction "3_3") (pintype "unspecified"))
      (node (ref "FPC2") (pin "6") (pinfunction "6_6") (pintype "unspecified"))
      (node (ref "FPC3") (pin "11") (pinfunction "11_11") (pintype "unspecified"))
      (node (ref "FPC3") (pin "12") (pinfunction "12_12") (pintype "unspecified"))
      (node (ref "FPC3") (pin "14") (pinfunction "14_14") (pintype "unspecified"))
      (node (ref "FPC4") (pin "5") (pinfunction "5_5") (pintype "input"))
      (node (ref "L1") (pin "1") (pinfunction "1_1") (pintype "input"))
      (node (ref "R7") (pin "2") (pinfunction "2_2") (pintype "unspecified"))
      (node (ref "TP2") (pin "1") (pinfunction "1_1") (pintype "input"))
      (node (ref "U1") (pin "8") (pinfunction "VCC_8") (pintype "input"))
      (node (ref "U5") (pin "6") (pinfunction "IN_6") (pintype "input"))
    )
    (net (code "39") (name "unconnected-(FPC1-Pad4)") (class "Default")
      (node (ref "FPC1") (pin "4") (pinfunction "4_4") (pintype "unspecified+no_connect"))
    )
    (net (code "40") (name "unconnected-(FPC1-Pad6)") (class "Default")
      (node (ref "FPC1") (pin "6") (pinfunction "6_6") (pintype "unspecified+no_connect"))
    )
    (net (code "41") (name "unconnected-(FPC1-Pad8)") (class "Default")
      (node (ref "FPC1") (pin "8") (pinfunction "8_8") (pintype "unspecified+no_connect"))
    )
    (net (code "42") (name "unconnected-(FPC1-Pad9)") (class "Default")
      (node (ref "FPC1") (pin "9") (pinfunction "9_9") (pintype "unspecified+no_connect"))
    )
    (net (code "43") (name "unconnected-(FPC1-Pad20)") (class "Default")
      (node (ref "FPC1") (pin "20") (pinfunction "20_20") (pintype "unspecified+no_connect"))
    )
    (net (code "44") (name "unconnected-(FPC1-Pad21)") (class "Default")
      (node (ref "FPC1") (pin "21") (pinfunction "21_21") (pintype "unspecified+no_connect"))
    )
    (net (code "45") (name "unconnected-(FPC1-Pad28)") (class "Default")
      (node (ref "FPC1") (pin "28") (pinfunction "28_28") (pintype "unspecified+no_connect"))
    )
    (net (code "46") (name "unconnected-(FPC3-Pad16)") (class "Default")
      (node (ref "FPC3") (pin "16") (pinfunction "16_16") (pintype "unspecified+no_connect"))
    )
    (net (code "47") (name "unconnected-(FPC3-Pad20)") (class "Default")
      (node (ref "FPC3") (pin "20") (pinfunction "20_20") (pintype "unspecified+no_connect"))
    )
    (net (code "48") (name "unconnected-(FPC3-Pad21)") (class "Default")
      (node (ref "FPC3") (pin "21") (pinfunction "21_21") (pintype "unspecified+no_connect"))
    )
    (net (code "49") (name "unconnected-(R14-Pad1)") (class "Default")
      (node (ref "R14") (pin "1") (pinfunction "1_1") (pintype "unspecified+no_connect"))
    )
    (net (code "50") (name "unconnected-(U1-NC-Pad3)") (class "Default")
      (node (ref "U1") (pin "3") (pinfunction "NC_3") (pintype "input+no_connect"))
    )
    (net (code "51") (name "unconnected-(U1-NC-Pad4)") (class "Default")
      (node (ref "U1") (pin "4") (pinfunction "NC_4") (pintype "input+no_connect"))
    )
    (net (code "52") (name "unconnected-(U11-DUMMY-Pad3)") (class "Default")
      (node (ref "U11") (pin "3") (pinfunction "DUMMY_3") (pintype "unspecified+no_connect"))
    )
    (net (code "53") (name "unconnected-(U11-DUMMY-Pad4)") (class "Default")
      (node (ref "U11") (pin "4") (pinfunction "DUMMY_4") (pintype "unspecified+no_connect"))
    )
  )
)
